# updated_PCB.net
KiCad netlist of a schematic drawn in EAGLE
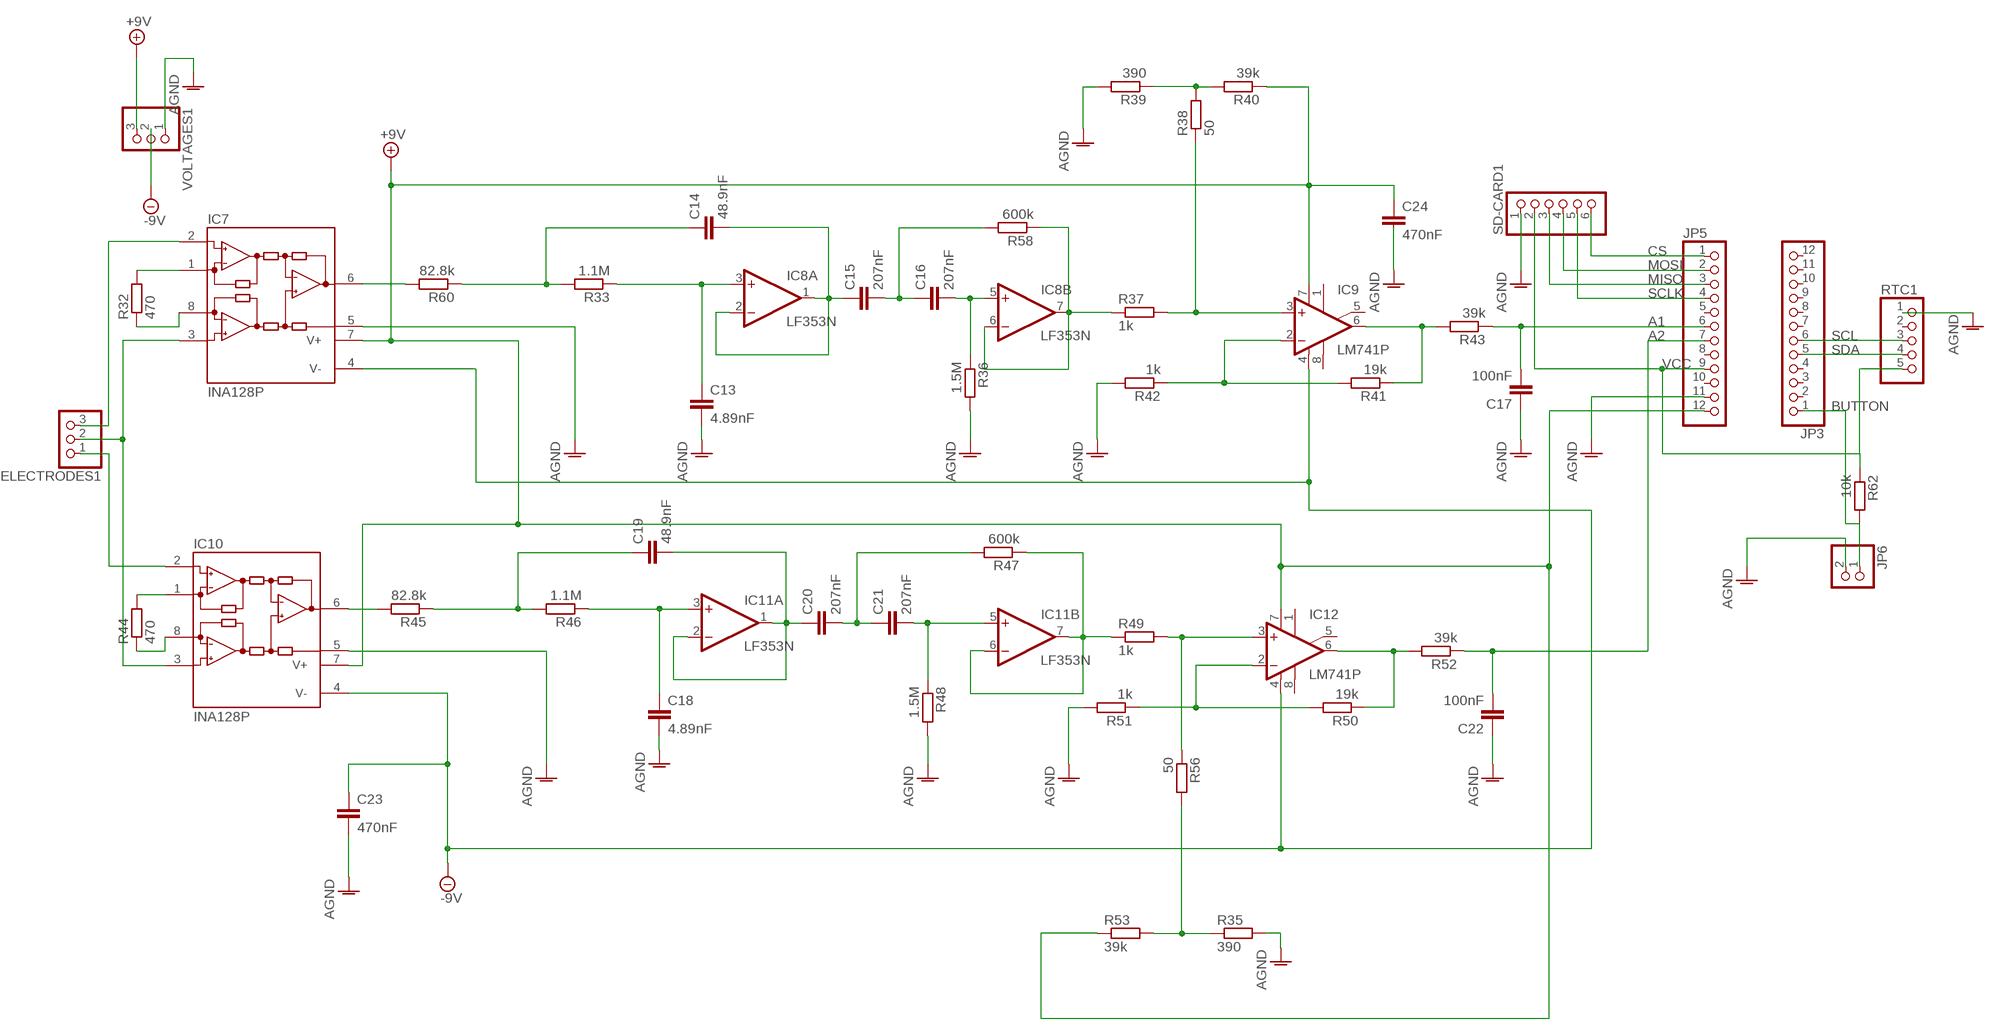
[diagram p0: schematic, sheet 1]

(export (version "E")
  (design (tool "Eeschema 10.0.6"))
  (components
    (comp (ref "C13")
      (value "4.89nF")
      (footprint "eagle-import:C025-030X050")
      (libsource (lib "eagle-import") (part "C-EU025-030X050"))
    )
    (comp (ref "C14")
      (value "48.9nF")
      (footprint "eagle-import:C025-030X050")
      (libsource (lib "eagle-import") (part "C-EU025-030X050"))
    )
    (comp (ref "C15")
      (value "207nF")
      (footprint "eagle-import:C025-030X050")
      (libsource (lib "eagle-import") (part "C-EU025-030X050"))
    )
    (comp (ref "C16")
      (value "207nF")
      (footprint "eagle-import:C025-030X050")
      (libsource (lib "eagle-import") (part "C-EU025-030X050"))
    )
    (comp (ref "C17")
      (value "100nF")
      (footprint "eagle-import:C025-030X050")
      (libsource (lib "eagle-import") (part "C-EU025-030X050"))
    )
    (comp (ref "C18")
      (value "4.89nF")
      (footprint "eagle-import:C025-030X050")
      (libsource (lib "eagle-import") (part "C-EU025-030X050"))
    )
    (comp (ref "C19")
      (value "48.9nF")
      (footprint "eagle-import:C025-030X050")
      (libsource (lib "eagle-import") (part "C-EU025-030X050"))
    )
    (comp (ref "C20")
      (value "207nF")
      (footprint "eagle-import:C025-030X050")
      (libsource (lib "eagle-import") (part "C-EU025-030X050"))
    )
    (comp (ref "C21")
      (value "207nF")
      (footprint "eagle-import:C025-030X050")
      (libsource (lib "eagle-import") (part "C-EU025-030X050"))
    )
    (comp (ref "C22")
      (value "100nF")
      (footprint "eagle-import:C025-030X050")
      (libsource (lib "eagle-import") (part "C-EU025-030X050"))
    )
    (comp (ref "C23")
      (value "470nF")
      (footprint "eagle-import:C025-030X050")
      (libsource (lib "eagle-import") (part "C-EU025-030X050"))
    )
    (comp (ref "C24")
      (value "470nF")
      (footprint "eagle-import:C025-030X050")
      (libsource (lib "eagle-import") (part "C-EU025-030X050"))
    )
    (comp (ref "ELECTRODES1")
      (value "PINHD-1X3")
      (footprint "eagle-import:1X03")
      (libsource (lib "eagle-import") (part "PINHD-1X3"))
    )
    (comp (ref "IC7")
      (value "INA128P")
      (footprint "eagle-import:DIL08")
      (fields (field (name "MF") "TEXAS INSTRUMENTS"))
      (libsource (lib "eagle-import") (part "INA128P"))
    )
    (comp (ref "IC8")
      (value "LF353N")
      (footprint "eagle-import:DIL08")
      (libsource (lib "eagle-import") (part "LF353N"))
    )
    (comp (ref "IC9")
      (value "LM741P")
      (footprint "eagle-import:DIL08")
      (libsource (lib "eagle-import") (part "741PLM"))
    )
    (comp (ref "IC10")
      (value "INA128P")
      (footprint "eagle-import:DIL08")
      (fields (field (name "MF") "TEXAS INSTRUMENTS"))
      (libsource (lib "eagle-import") (part "INA128P"))
    )
    (comp (ref "IC11")
      (value "LF353N")
      (footprint "eagle-import:DIL08")
      (libsource (lib "eagle-import") (part "LF353N"))
    )
    (comp (ref "IC12")
      (value "LM741P")
      (footprint "eagle-import:DIL08")
      (libsource (lib "eagle-import") (part "741PLM"))
    )
    (comp (ref "JP3")
      (value "PINHD-1X12")
      (footprint "eagle-import:1X12")
      (libsource (lib "eagle-import") (part "PINHD-1X12"))
    )
    (comp (ref "JP5")
      (value "PINHD-1X12")
      (footprint "eagle-import:1X12")
      (libsource (lib "eagle-import") (part "PINHD-1X12"))
    )
    (comp (ref "JP6")
      (value "PINHD-1X2")
      (footprint "eagle-import:1X02")
      (libsource (lib "eagle-import") (part "PINHD-1X2"))
    )
    (comp (ref "R32")
      (value "470")
      (footprint "eagle-import:0309_12")
      (libsource (lib "eagle-import") (part "R-EU_0309/12"))
    )
    (comp (ref "R33")
      (value "1.1M")
      (footprint "eagle-import:0309_12")
      (libsource (lib "eagle-import") (part "R-EU_0309/12"))
    )
    (comp (ref "R35")
      (value "390")
      (footprint "eagle-import:0309_12")
      (libsource (lib "eagle-import") (part "R-EU_0309/12"))
    )
    (comp (ref "R36")
      (value "1.5M")
      (footprint "eagle-import:0309_12")
      (libsource (lib "eagle-import") (part "R-EU_0309/12"))
    )
    (comp (ref "R37")
      (value "1k")
      (footprint "eagle-import:0309_12")
      (libsource (lib "eagle-import") (part "R-EU_0309/12"))
    )
    (comp (ref "R38")
      (value "50")
      (footprint "eagle-import:0309_12")
      (libsource (lib "eagle-import") (part "R-EU_0309/12"))
    )
    (comp (ref "R39")
      (value "390")
      (footprint "eagle-import:0309_12")
      (libsource (lib "eagle-import") (part "R-EU_0309/12"))
    )
    (comp (ref "R40")
      (value "39k")
      (footprint "eagle-import:0309_12")
      (libsource (lib "eagle-import") (part "R-EU_0309/12"))
    )
    (comp (ref "R41")
      (value "19k")
      (footprint "eagle-import:0309_12")
      (libsource (lib "eagle-import") (part "R-EU_0309/12"))
    )
    (comp (ref "R42")
      (value "1k")
      (footprint "eagle-import:0309_12")
      (libsource (lib "eagle-import") (part "R-EU_0309/12"))
    )
    (comp (ref "R43")
      (value "39k")
      (footprint "eagle-import:0309_12")
      (libsource (lib "eagle-import") (part "R-EU_0309/12"))
    )
    (comp (ref "R44")
      (value "470")
      (footprint "eagle-import:0309_12")
      (libsource (lib "eagle-import") (part "R-EU_0309/12"))
    )
    (comp (ref "R45")
      (value "82.8k")
      (footprint "eagle-import:0309_12")
      (libsource (lib "eagle-import") (part "R-EU_0309/12"))
    )
    (comp (ref "R46")
      (value "1.1M")
      (footprint "eagle-import:0309_12")
      (libsource (lib "eagle-import") (part "R-EU_0309/12"))
    )
    (comp (ref "R47")
      (value "600k")
      (footprint "eagle-import:0309_12")
      (libsource (lib "eagle-import") (part "R-EU_0309/12"))
    )
    (comp (ref "R48")
      (value "1.5M")
      (footprint "eagle-import:0309_12")
      (libsource (lib "eagle-import") (part "R-EU_0309/12"))
    )
    (comp (ref "R49")
      (value "1k")
      (footprint "eagle-import:0309_12")
      (libsource (lib "eagle-import") (part "R-EU_0309/12"))
    )
    (comp (ref "R50")
      (value "19k")
      (footprint "eagle-import:0309_12")
      (libsource (lib "eagle-import") (part "R-EU_0309/12"))
    )
    (comp (ref "R51")
      (value "1k")
      (footprint "eagle-import:0309_12")
      (libsource (lib "eagle-import") (part "R-EU_0309/12"))
    )
    (comp (ref "R52")
      (value "39k")
      (footprint "eagle-import:0309_12")
      (libsource (lib "eagle-import") (part "R-EU_0309/12"))
    )
    (comp (ref "R53")
      (value "39k")
      (footprint "eagle-import:0309_12")
      (libsource (lib "eagle-import") (part "R-EU_0309/12"))
    )
    (comp (ref "R56")
      (value "50")
      (footprint "eagle-import:0309_12")
      (libsource (lib "eagle-import") (part "R-EU_0309/12"))
    )
    (comp (ref "R58")
      (value "600k")
      (footprint "eagle-import:0309_12")
      (libsource (lib "eagle-import") (part "R-EU_0309/12"))
    )
    (comp (ref "R60")
      (value "82.8k")
      (footprint "eagle-import:0309_12")
      (libsource (lib "eagle-import") (part "R-EU_0309/12"))
    )
    (comp (ref "R62")
      (value "10k")
      (footprint "eagle-import:0309_12")
      (libsource (lib "eagle-import") (part "R-EU_0309/12"))
    )
    (comp (ref "RTC1")
      (value "PINHD-1X5")
      (footprint "eagle-import:1X05")
      (libsource (lib "eagle-import") (part "PINHD-1X5"))
    )
    (comp (ref "SD-CARD1")
      (value "PINHD-1X6")
      (footprint "eagle-import:1X06")
      (libsource (lib "eagle-import") (part "PINHD-1X6"))
    )
    (comp (ref "VOLTAGES1")
      (value "PINHD-1X3")
      (footprint "eagle-import:1X03")
      (libsource (lib "eagle-import") (part "PINHD-1X3"))
    )
  )
  (nets
    (net (code "1") (name "+9V") (class "Default")
      (node (ref "C24") (pin "1") (pinfunction "1_1") (pintype "passive"))
      (node (ref "IC10") (pin "7") (pinfunction "V+_7") (pintype "power_in"))
      (node (ref "IC12") (pin "7") (pinfunction "V+_7") (pintype "power_in"))
      (node (ref "IC7") (pin "7") (pinfunction "V+_7") (pintype "power_in"))
      (node (ref "IC9") (pin "7") (pinfunction "V+_7") (pintype "power_in"))
      (node (ref "JP5") (pin "12") (pinfunction "12_12") (pintype "passive"))
      (node (ref "R40") (pin "1") (pinfunction "1_1") (pintype "passive"))
      (node (ref "R53") (pin "1") (pinfunction "1_1") (pintype "passive"))
      (node (ref "VOLTAGES1") (pin "3") (pinfunction "3_3") (pintype "passive"))
    )
    (net (code "2") (name "-9V") (class "Default")
      (node (ref "C23") (pin "1") (pinfunction "1_1") (pintype "passive"))
      (node (ref "IC10") (pin "4") (pinfunction "V-_4") (pintype "power_in"))
      (node (ref "IC12") (pin "4") (pinfunction "V-_4") (pintype "power_in"))
      (node (ref "IC7") (pin "4") (pinfunction "V-_4") (pintype "power_in"))
      (node (ref "IC9") (pin "4") (pinfunction "V-_4") (pintype "power_in"))
      (node (ref "VOLTAGES1") (pin "2") (pinfunction "2_2") (pintype "passive"))
    )
    (net (code "3") (name "/A1") (class "Default")
      (node (ref "C17") (pin "2") (pinfunction "2_2") (pintype "passive"))
      (node (ref "JP5") (pin "6") (pinfunction "6_6") (pintype "passive"))
      (node (ref "R43") (pin "1") (pinfunction "1_1") (pintype "passive"))
    )
    (net (code "4") (name "/A2") (class "Default")
      (node (ref "C22") (pin "2") (pinfunction "2_2") (pintype "passive"))
      (node (ref "JP5") (pin "7") (pinfunction "7_7") (pintype "passive"))
      (node (ref "R52") (pin "1") (pinfunction "1_1") (pintype "passive"))
    )
    (net (code "5") (name "/BUTTON") (class "Default")
      (node (ref "JP3") (pin "1") (pinfunction "1_1") (pintype "passive"))
      (node (ref "JP6") (pin "1") (pinfunction "1_1") (pintype "passive"))
      (node (ref "R62") (pin "2") (pinfunction "2_2") (pintype "passive"))
    )
    (net (code "6") (name "/CS") (class "Default")
      (node (ref "JP5") (pin "1") (pinfunction "1_1") (pintype "passive"))
      (node (ref "SD-CARD1") (pin "6") (pinfunction "6_6") (pintype "passive"))
    )
    (net (code "7") (name "/MISO") (class "Default")
      (node (ref "JP5") (pin "3") (pinfunction "3_3") (pintype "passive"))
      (node (ref "SD-CARD1") (pin "3") (pinfunction "3_3") (pintype "passive"))
    )
    (net (code "8") (name "/MOSI") (class "Default")
      (node (ref "JP5") (pin "2") (pinfunction "2_2") (pintype "passive"))
      (node (ref "SD-CARD1") (pin "4") (pinfunction "4_4") (pintype "passive"))
    )
    (net (code "9") (name "/SCL") (class "Default")
      (node (ref "JP3") (pin "6") (pinfunction "6_6") (pintype "passive"))
      (node (ref "RTC1") (pin "3") (pinfunction "3_3") (pintype "passive"))
    )
    (net (code "10") (name "/SCLK") (class "Default")
      (node (ref "JP5") (pin "4") (pinfunction "4_4") (pintype "passive"))
      (node (ref "SD-CARD1") (pin "5") (pinfunction "5_5") (pintype "passive"))
    )
    (net (code "11") (name "/SDA") (class "Default")
      (node (ref "JP3") (pin "5") (pinfunction "5_5") (pintype "passive"))
      (node (ref "RTC1") (pin "4") (pinfunction "4_4") (pintype "passive"))
    )
    (net (code "12") (name "/VCC") (class "Default")
      (node (ref "JP5") (pin "9") (pinfunction "9_9") (pintype "passive"))
      (node (ref "R62") (pin "1") (pinfunction "1_1") (pintype "passive"))
      (node (ref "RTC1") (pin "5") (pinfunction "5_5") (pintype "passive"))
      (node (ref "SD-CARD1") (pin "2") (pinfunction "2_2") (pintype "passive"))
    )
    (net (code "13") (name "AGND") (class "Default")
      (node (ref "C13") (pin "2") (pinfunction "2_2") (pintype "passive"))
      (node (ref "C17") (pin "1") (pinfunction "1_1") (pintype "passive"))
      (node (ref "C18") (pin "2") (pinfunction "2_2") (pintype "passive"))
      (node (ref "C22") (pin "1") (pinfunction "1_1") (pintype "passive"))
      (node (ref "C23") (pin "2") (pinfunction "2_2") (pintype "passive"))
      (node (ref "IC10") (pin "5") (pinfunction "REF_5") (pintype "passive"))
      (node (ref "IC7") (pin "5") (pinfunction "REF_5") (pintype "passive"))
      (node (ref "JP5") (pin "11") (pinfunction "11_11") (pintype "passive"))
      (node (ref "JP6") (pin "2") (pinfunction "2_2") (pintype "passive"))
      (node (ref "R35") (pin "2") (pinfunction "2_2") (pintype "passive"))
      (node (ref "R36") (pin "2") (pinfunction "2_2") (pintype "passive"))
      (node (ref "R39") (pin "2") (pinfunction "2_2") (pintype "passive"))
      (node (ref "R42") (pin "2") (pinfunction "2_2") (pintype "passive"))
      (node (ref "R48") (pin "2") (pinfunction "2_2") (pintype "passive"))
      (node (ref "R51") (pin "2") (pinfunction "2_2") (pintype "passive"))
      (node (ref "RTC1") (pin "1") (pinfunction "1_1") (pintype "passive"))
      (node (ref "SD-CARD1") (pin "1") (pinfunction "1_1") (pintype "passive"))
      (node (ref "VOLTAGES1") (pin "1") (pinfunction "1_1") (pintype "passive"))
    )
    (net (code "14") (name "Net-(C14-Pad1)") (class "Default")
      (node (ref "C14") (pin "1") (pinfunction "1_1") (pintype "passive"))
      (node (ref "R33") (pin "2") (pinfunction "2_2") (pintype "passive"))
      (node (ref "R60") (pin "1") (pinfunction "1_1") (pintype "passive"))
    )
    (net (code "15") (name "Net-(C15-Pad2)") (class "Default")
      (node (ref "C15") (pin "2") (pinfunction "2_2") (pintype "passive"))
      (node (ref "C16") (pin "1") (pinfunction "1_1") (pintype "passive"))
      (node (ref "R58") (pin "2") (pinfunction "2_2") (pintype "passive"))
    )
    (net (code "16") (name "Net-(C19-Pad1)") (class "Default")
      (node (ref "C19") (pin "1") (pinfunction "1_1") (pintype "passive"))
      (node (ref "R45") (pin "1") (pinfunction "1_1") (pintype "passive"))
      (node (ref "R46") (pin "2") (pinfunction "2_2") (pintype "passive"))
    )
    (net (code "17") (name "Net-(C20-Pad2)") (class "Default")
      (node (ref "C20") (pin "2") (pinfunction "2_2") (pintype "passive"))
      (node (ref "C21") (pin "1") (pinfunction "1_1") (pintype "passive"))
      (node (ref "R47") (pin "2") (pinfunction "2_2") (pintype "passive"))
    )
    (net (code "18") (name "Net-(IC7--IN)") (class "Default")
      (node (ref "ELECTRODES1") (pin "3") (pinfunction "3_3") (pintype "passive"))
      (node (ref "IC7") (pin "2") (pinfunction "-IN_2") (pintype "input"))
    )
    (net (code "19") (name "Net-(IC7-OUT)") (class "Default")
      (node (ref "IC7") (pin "6") (pinfunction "OUT_6") (pintype "output"))
      (node (ref "R60") (pin "2") (pinfunction "2_2") (pintype "passive"))
    )
    (net (code "20") (name "Net-(IC7-RG-Pad1)") (class "Default")
      (node (ref "IC7") (pin "1") (pinfunction "RG_1") (pintype "passive"))
      (node (ref "R32") (pin "2") (pinfunction "2_2") (pintype "passive"))
    )
    (net (code "21") (name "Net-(IC7-RG-Pad8)") (class "Default")
      (node (ref "IC7") (pin "8") (pinfunction "RG_8") (pintype "passive"))
      (node (ref "R32") (pin "1") (pinfunction "1_1") (pintype "passive"))
    )
    (net (code "22") (name "Net-(IC8A-+IN)") (class "Default")
      (node (ref "C13") (pin "1") (pinfunction "1_1") (pintype "passive"))
      (node (ref "IC8") (pin "3") (pinfunction "+IN_3") (pintype "input"))
      (node (ref "R33") (pin "1") (pinfunction "1_1") (pintype "passive"))
    )
    (net (code "23") (name "Net-(IC8A--IN)") (class "Default")
      (node (ref "C14") (pin "2") (pinfunction "2_2") (pintype "passive"))
      (node (ref "C15") (pin "1") (pinfunction "1_1") (pintype "passive"))
      (node (ref "IC8") (pin "1") (pinfunction "OUT_1") (pintype "output"))
      (node (ref "IC8") (pin "2") (pinfunction "-IN_2") (pintype "input"))
    )
    (net (code "24") (name "Net-(IC8B-+IN)") (class "Default")
      (node (ref "C16") (pin "2") (pinfunction "2_2") (pintype "passive"))
      (node (ref "IC8") (pin "5") (pinfunction "+IN_5") (pintype "input"))
      (node (ref "R36") (pin "1") (pinfunction "1_1") (pintype "passive"))
    )
    (net (code "25") (name "Net-(IC8B--IN)") (class "Default")
      (node (ref "IC8") (pin "6") (pinfunction "-IN_6") (pintype "input"))
      (node (ref "IC8") (pin "7") (pinfunction "OUT_7") (pintype "output"))
      (node (ref "R37") (pin "1") (pinfunction "1_1") (pintype "passive"))
      (node (ref "R58") (pin "1") (pinfunction "1_1") (pintype "passive"))
    )
    (net (code "26") (name "Net-(IC9-+IN)") (class "Default")
      (node (ref "IC9") (pin "3") (pinfunction "+IN_3") (pintype "input"))
      (node (ref "R37") (pin "2") (pinfunction "2_2") (pintype "passive"))
      (node (ref "R38") (pin "1") (pinfunction "1_1") (pintype "passive"))
    )
    (net (code "27") (name "Net-(IC9--IN)") (class "Default")
      (node (ref "IC9") (pin "2") (pinfunction "-IN_2") (pintype "input"))
      (node (ref "R41") (pin "2") (pinfunction "2_2") (pintype "passive"))
      (node (ref "R42") (pin "1") (pinfunction "1_1") (pintype "passive"))
    )
    (net (code "28") (name "Net-(IC9-OUT)") (class "Default")
      (node (ref "IC9") (pin "6") (pinfunction "OUT_6") (pintype "output"))
      (node (ref "R41") (pin "1") (pinfunction "1_1") (pintype "passive"))
      (node (ref "R43") (pin "2") (pinfunction "2_2") (pintype "passive"))
    )
    (net (code "29") (name "Net-(IC10-+IN)") (class "Default")
      (node (ref "ELECTRODES1") (pin "2") (pinfunction "2_2") (pintype "passive"))
      (node (ref "IC10") (pin "3") (pinfunction "+IN_3") (pintype "input"))
      (node (ref "IC7") (pin "3") (pinfunction "+IN_3") (pintype "input"))
    )
    (net (code "30") (name "Net-(IC10--IN)") (class "Default")
      (node (ref "ELECTRODES1") (pin "1") (pinfunction "1_1") (pintype "passive"))
      (node (ref "IC10") (pin "2") (pinfunction "-IN_2") (pintype "input"))
    )
    (net (code "31") (name "Net-(IC10-OUT)") (class "Default")
      (node (ref "IC10") (pin "6") (pinfunction "OUT_6") (pintype "output"))
      (node (ref "R45") (pin "2") (pinfunction "2_2") (pintype "passive"))
    )
    (net (code "32") (name "Net-(IC10-RG-Pad1)") (class "Default")
      (node (ref "IC10") (pin "1") (pinfunction "RG_1") (pintype "passive"))
      (node (ref "R44") (pin "2") (pinfunction "2_2") (pintype "passive"))
    )
    (net (code "33") (name "Net-(IC10-RG-Pad8)") (class "Default")
      (node (ref "IC10") (pin "8") (pinfunction "RG_8") (pintype "passive"))
      (node (ref "R44") (pin "1") (pinfunction "1_1") (pintype "passive"))
    )
    (net (code "34") (name "Net-(IC11A-+IN)") (class "Default")
      (node (ref "C18") (pin "1") (pinfunction "1_1") (pintype "passive"))
      (node (ref "IC11") (pin "3") (pinfunction "+IN_3") (pintype "input"))
      (node (ref "R46") (pin "1") (pinfunction "1_1") (pintype "passive"))
    )
    (net (code "35") (name "Net-(IC11A--IN)") (class "Default")
      (node (ref "C19") (pin "2") (pinfunction "2_2") (pintype "passive"))
      (node (ref "C20") (pin "1") (pinfunction "1_1") (pintype "passive"))
      (node (ref "IC11") (pin "1") (pinfunction "OUT_1") (pintype "output"))
      (node (ref "IC11") (pin "2") (pinfunction "-IN_2") (pintype "input"))
    )
    (net (code "36") (name "Net-(IC11B-+IN)") (class "Default")
      (node (ref "C21") (pin "2") (pinfunction "2_2") (pintype "passive"))
      (node (ref "IC11") (pin "5") (pinfunction "+IN_5") (pintype "input"))
      (node (ref "R48") (pin "1") (pinfunction "1_1") (pintype "passive"))
    )
    (net (code "37") (name "Net-(IC11B--IN)") (class "Default")
      (node (ref "IC11") (pin "6") (pinfunction "-IN_6") (pintype "input"))
      (node (ref "IC11") (pin "7") (pinfunction "OUT_7") (pintype "output"))
      (node (ref "R47") (pin "1") (pinfunction "1_1") (pintype "passive"))
      (node (ref "R49") (pin "1") (pinfunction "1_1") (pintype "passive"))
    )
    (net (code "38") (name "Net-(IC12-+IN)") (class "Default")
      (node (ref "IC12") (pin "3") (pinfunction "+IN_3") (pintype "input"))
      (node (ref "R49") (pin "2") (pinfunction "2_2") (pintype "passive"))
      (node (ref "R56") (pin "1") (pinfunction "1_1") (pintype "passive"))
    )
    (net (code "39") (name "Net-(IC12--IN)") (class "Default")
      (node (ref "IC12") (pin "2") (pinfunction "-IN_2") (pintype "input"))
      (node (ref "R50") (pin "2") (pinfunction "2_2") (pintype "passive"))
      (node (ref "R51") (pin "1") (pinfunction "1_1") (pintype "passive"))
    )
    (net (code "40") (name "Net-(IC12-OUT)") (class "Default")
      (node (ref "IC12") (pin "6") (pinfunction "OUT_6") (pintype "output"))
      (node (ref "R50") (pin "1") (pinfunction "1_1") (pintype "passive"))
      (node (ref "R52") (pin "2") (pinfunction "2_2") (pintype "passive"))
    )
    (net (code "41") (name "Net-(R35-Pad1)") (class "Default")
      (node (ref "R35") (pin "1") (pinfunction "1_1") (pintype "passive"))
      (node (ref "R53") (pin "2") (pinfunction "2_2") (pintype "passive"))
      (node (ref "R56") (pin "2") (pinfunction "2_2") (pintype "passive"))
    )
    (net (code "42") (name "Net-(R38-Pad2)") (class "Default")
      (node (ref "R38") (pin "2") (pinfunction "2_2") (pintype "passive"))
      (node (ref "R39") (pin "1") (pinfunction "1_1") (pintype "passive"))
      (node (ref "R40") (pin "2") (pinfunction "2_2") (pintype "passive"))
    )
    (net (code "43") (name "unconnected-(C24-Pad2)") (class "Default")
      (node (ref "C24") (pin "2") (pinfunction "2_2") (pintype "passive"))
    )
    (net (code "44") (name "unconnected-(IC9-ON1-Pad1)") (class "Default")
      (node (ref "IC9") (pin "1") (pinfunction "ON1_1") (pintype "passive"))
    )
    (net (code "45") (name "unconnected-(IC9-ON2-Pad5)") (class "Default")
      (node (ref "IC9") (pin "5") (pinfunction "ON2_5") (pintype "passive"))
    )
    (net (code "46") (name "unconnected-(IC9-OPT-Pad8)") (class "Default")
      (node (ref "IC9") (pin "8") (pinfunction "OPT_8") (pintype "passive"))
    )
    (net (code "47") (name "unconnected-(IC12-ON1-Pad1)") (class "Default")
      (node (ref "IC12") (pin "1") (pinfunction "ON1_1") (pintype "passive"))
    )
    (net (code "48") (name "unconnected-(IC12-ON2-Pad5)") (class "Default")
      (node (ref "IC12") (pin "5") (pinfunction "ON2_5") (pintype "passive"))
    )
    (net (code "49") (name "unconnected-(IC12-OPT-Pad8)") (class "Default")
      (node (ref "IC12") (pin "8") (pinfunction "OPT_8") (pintype "passive"))
    )
    (net (code "50") (name "unconnected-(JP3-Pad2)") (class "Default")
      (node (ref "JP3") (pin "2") (pinfunction "2_2") (pintype "passive"))
    )
    (net (code "51") (name "unconnected-(JP3-Pad3)") (class "Default")
      (node (ref "JP3") (pin "3") (pinfunction "3_3") (pintype "passive"))
    )
    (net (code "52") (name "unconnected-(JP3-Pad4)") (class "Default")
      (node (ref "JP3") (pin "4") (pinfunction "4_4") (pintype "passive"))
    )
    (net (code "53") (name "unconnected-(JP3-Pad7)") (class "Default")
      (node (ref "JP3") (pin "7") (pinfunction "7_7") (pintype "passive"))
    )
    (net (code "54") (name "unconnected-(JP3-Pad8)") (class "Default")
      (node (ref "JP3") (pin "8") (pinfunction "8_8") (pintype "passive"))
    )
    (net (code "55") (name "unconnected-(JP3-Pad9)") (class "Default")
      (node (ref "JP3") (pin "9") (pinfunction "9_9") (pintype "passive"))
    )
    (net (code "56") (name "unconnected-(JP3-Pad10)") (class "Default")
      (node (ref "JP3") (pin "10") (pinfunction "10_10") (pintype "passive"))
    )
    (net (code "57") (name "unconnected-(JP3-Pad11)") (class "Default")
      (node (ref "JP3") (pin "11") (pinfunction "11_11") (pintype "passive"))
    )
    (net (code "58") (name "unconnected-(JP3-Pad12)") (class "Default")
      (node (ref "JP3") (pin "12") (pinfunction "12_12") (pintype "passive"))
    )
    (net (code "59") (name "unconnected-(JP5-Pad5)") (class "Default")
      (node (ref "JP5") (pin "5") (pinfunction "5_5") (pintype "passive"))
    )
    (net (code "60") (name "unconnected-(JP5-Pad8)") (class "Default")
      (node (ref "JP5") (pin "8") (pinfunction "8_8") (pintype "passive"))
    )
    (net (code "61") (name "unconnected-(JP5-Pad10)") (class "Default")
      (node (ref "JP5") (pin "10") (pinfunction "10_10") (pintype "passive"))
    )
    (net (code "62") (name "unconnected-(RTC1-Pad2)") (class "Default")
      (node (ref "RTC1") (pin "2") (pinfunction "2_2") (pintype "passive"))
    )
  )
)
